# 00_EEG_AFE.net
KiCad netlist of a schematic drawn in Altium Designer
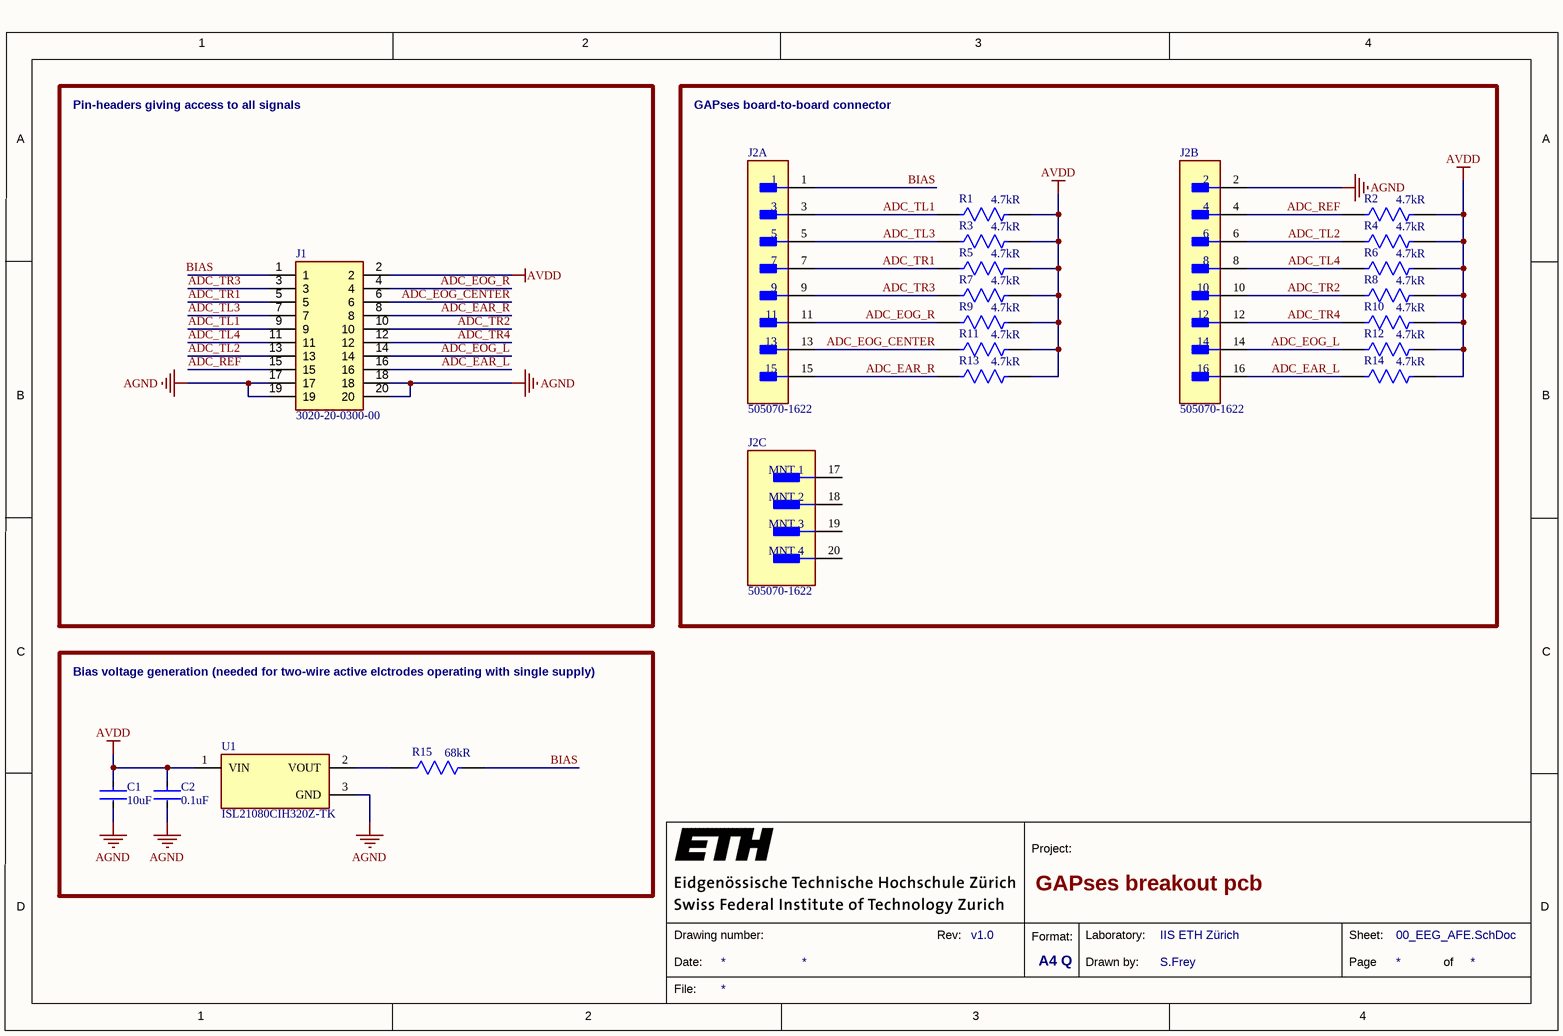
[diagram p0: 00_EEG_AFE.SchDoc]

(export (version "E")
  (design (tool "Eeschema 10.0.6"))
  (components
    (comp (ref "C1")
      (value "CL05A106MP8NUB8")
      (footprint "FP-CL07-IPC_C")
      (description "Cap Ceramic 10uF 10V X5R ±20% SMD 0402 +85°C Paper T/R")
      (fields (field (name "CAPACITANCE") "10uF") (field (name "TOLERANCE") "20%"))
      (libsource (lib "Altium Content Vault") (part "b4654b650e69147ec39a6b967a45e02"))
    )
    (comp (ref "C2")
      (value "CL05A104KA5NNNC")
      (footprint "FP-CL278-IPC_C")
      (description "Cap Ceramic 100nF 25V X5R ±10% SMD 0402 +85°C Paper T/R")
      (fields
        (field (name "VOLTAGE") "25V")
        (field (name "TOLERANCE") "10%")
        (field (name "CAPACITANCE") "0.1uF")
      )
      (libsource (lib "Altium Content Vault") (part "b4654b650e69147ec39a6b967a45e02"))
    )
    (comp (ref "J1")
      (value "3020-20-0300-00")
      (footprint "SamacSys:302020030000")
      (description "Connector")
      (libsource (lib "SamacSys") (part "3020-20-0300-00"))
    )
    (comp (ref "J2")
      (value "505070-1622")
      (footprint "FP-505070-1622-MFG")
      (description "CONN PLUG 16POS SMD GOLD")
      (libsource (lib "Altium Content Vault") (part "71c7bd868a703cb05f67e14b15c5ca9"))
    )
    (comp (ref "R1")
      (value "RR0510P-472-D")
      (footprint "FP-RR0510-IPC_C")
      (description "4.7kΩ ±0.5% 0.0625W 1/16W Chip Resistor 0402 (1005 Metric) Thin Film")
      (fields (field (name "TOLERANCE") "0.5%") (field (name "RESISTANCE") "4.7kR"))
      (libsource (lib "Altium Content Vault") (part "1029c3af85768c4190bb7ad29bc67b5"))
    )
    (comp (ref "R2")
      (value "RR0510P-472-D")
      (footprint "FP-RR0510-IPC_C")
      (description "4.7kΩ ±0.5% 0.0625W 1/16W Chip Resistor 0402 (1005 Metric) Thin Film")
      (fields (field (name "TOLERANCE") "0.5%") (field (name "RESISTANCE") "4.7kR"))
      (libsource (lib "Altium Content Vault") (part "1029c3af85768c4190bb7ad29bc67b5"))
    )
    (comp (ref "R3")
      (value "RR0510P-472-D")
      (footprint "FP-RR0510-IPC_C")
      (description "4.7kΩ ±0.5% 0.0625W 1/16W Chip Resistor 0402 (1005 Metric) Thin Film")
      (fields (field (name "TOLERANCE") "0.5%") (field (name "RESISTANCE") "4.7kR"))
      (libsource (lib "Altium Content Vault") (part "1029c3af85768c4190bb7ad29bc67b5"))
    )
    (comp (ref "R4")
      (value "RR0510P-472-D")
      (footprint "FP-RR0510-IPC_C")
      (description "4.7kΩ ±0.5% 0.0625W 1/16W Chip Resistor 0402 (1005 Metric) Thin Film")
      (fields (field (name "TOLERANCE") "0.5%") (field (name "RESISTANCE") "4.7kR"))
      (libsource (lib "Altium Content Vault") (part "1029c3af85768c4190bb7ad29bc67b5"))
    )
    (comp (ref "R5")
      (value "RR0510P-472-D")
      (footprint "FP-RR0510-IPC_C")
      (description "4.7kΩ ±0.5% 0.0625W 1/16W Chip Resistor 0402 (1005 Metric) Thin Film")
      (fields (field (name "TOLERANCE") "0.5%") (field (name "RESISTANCE") "4.7kR"))
      (libsource (lib "Altium Content Vault") (part "1029c3af85768c4190bb7ad29bc67b5"))
    )
    (comp (ref "R6")
      (value "RR0510P-472-D")
      (footprint "FP-RR0510-IPC_C")
      (description "4.7kΩ ±0.5% 0.0625W 1/16W Chip Resistor 0402 (1005 Metric) Thin Film")
      (fields (field (name "TOLERANCE") "0.5%") (field (name "RESISTANCE") "4.7kR"))
      (libsource (lib "Altium Content Vault") (part "1029c3af85768c4190bb7ad29bc67b5"))
    )
    (comp (ref "R7")
      (value "RR0510P-472-D")
      (footprint "FP-RR0510-IPC_C")
      (description "4.7kΩ ±0.5% 0.0625W 1/16W Chip Resistor 0402 (1005 Metric) Thin Film")
      (fields (field (name "TOLERANCE") "0.5%") (field (name "RESISTANCE") "4.7kR"))
      (libsource (lib "Altium Content Vault") (part "1029c3af85768c4190bb7ad29bc67b5"))
    )
    (comp (ref "R8")
      (value "RR0510P-472-D")
      (footprint "FP-RR0510-IPC_C")
      (description "4.7kΩ ±0.5% 0.0625W 1/16W Chip Resistor 0402 (1005 Metric) Thin Film")
      (fields (field (name "TOLERANCE") "0.5%") (field (name "RESISTANCE") "4.7kR"))
      (libsource (lib "Altium Content Vault") (part "1029c3af85768c4190bb7ad29bc67b5"))
    )
    (comp (ref "R9")
      (value "RR0510P-472-D")
      (footprint "FP-RR0510-IPC_C")
      (description "4.7kΩ ±0.5% 0.0625W 1/16W Chip Resistor 0402 (1005 Metric) Thin Film")
      (fields (field (name "TOLERANCE") "0.5%") (field (name "RESISTANCE") "4.7kR"))
      (libsource (lib "Altium Content Vault") (part "1029c3af85768c4190bb7ad29bc67b5"))
    )
    (comp (ref "R10")
      (value "RR0510P-472-D")
      (footprint "FP-RR0510-IPC_C")
      (description "4.7kΩ ±0.5% 0.0625W 1/16W Chip Resistor 0402 (1005 Metric) Thin Film")
      (fields (field (name "TOLERANCE") "0.5%") (field (name "RESISTANCE") "4.7kR"))
      (libsource (lib "Altium Content Vault") (part "1029c3af85768c4190bb7ad29bc67b5"))
    )
    (comp (ref "R11")
      (value "RR0510P-472-D")
      (footprint "FP-RR0510-IPC_C")
      (description "4.7kΩ ±0.5% 0.0625W 1/16W Chip Resistor 0402 (1005 Metric) Thin Film")
      (fields (field (name "TOLERANCE") "0.5%") (field (name "RESISTANCE") "4.7kR"))
      (libsource (lib "Altium Content Vault") (part "1029c3af85768c4190bb7ad29bc67b5"))
    )
    (comp (ref "R12")
      (value "RR0510P-472-D")
      (footprint "FP-RR0510-IPC_C")
      (description "4.7kΩ ±0.5% 0.0625W 1/16W Chip Resistor 0402 (1005 Metric) Thin Film")
      (fields (field (name "TOLERANCE") "0.5%") (field (name "RESISTANCE") "4.7kR"))
      (libsource (lib "Altium Content Vault") (part "1029c3af85768c4190bb7ad29bc67b5"))
    )
    (comp (ref "R13")
      (value "RR0510P-472-D")
      (footprint "FP-RR0510-IPC_C")
      (description "4.7kΩ ±0.5% 0.0625W 1/16W Chip Resistor 0402 (1005 Metric) Thin Film")
      (fields (field (name "TOLERANCE") "0.5%") (field (name "RESISTANCE") "4.7kR"))
      (libsource (lib "Altium Content Vault") (part "1029c3af85768c4190bb7ad29bc67b5"))
    )
    (comp (ref "R14")
      (value "RR0510P-472-D")
      (footprint "FP-RR0510-IPC_C")
      (description "4.7kΩ ±0.5% 0.0625W 1/16W Chip Resistor 0402 (1005 Metric) Thin Film")
      (fields (field (name "TOLERANCE") "0.5%") (field (name "RESISTANCE") "4.7kR"))
      (libsource (lib "Altium Content Vault") (part "1029c3af85768c4190bb7ad29bc67b5"))
    )
    (comp (ref "R15")
      (value "RR0510P-683-D")
      (footprint "FP-RR0510-MFG")
      (description "68kΩ ±0.5% 0.0625W 1/16W Chip Resistor 0402 (1005 Metric) Thin Film")
      (fields (field (name "TOLERANCE") "0.5%") (field (name "RESISTANCE") "68kR"))
      (libsource (lib "Altium Content Vault") (part "1029c3af85768c4190bb7ad29bc67b5"))
    )
    (comp (ref "U1")
      (value "ISL21080CIH320Z-TK")
      (footprint "FP-P3_064A-IPC_C")
      (description "IC VREF SERIES 0.3% SOT23-3")
      (fields (field (name "TOLERANCE") "0.3%"))
      (libsource (lib "Altium Content Vault") (part "d4f0b6a9f4a6a4d0e4630da6419d1e9"))
    )
  )
  (nets
    (net (code "1") (name "/ADC_EAR_L") (class "Default")
      (node (ref "J1") (pin "16") (pinfunction "16_16") (pintype "passive"))
      (node (ref "J2") (pin "16") (pinfunction "16_16") (pintype "passive"))
      (node (ref "R14") (pin "1") (pinfunction "1_1") (pintype "passive"))
    )
    (net (code "2") (name "/ADC_EAR_R") (class "Default")
      (node (ref "J1") (pin "8") (pinfunction "8_8") (pintype "passive"))
      (node (ref "J2") (pin "15") (pinfunction "15_15") (pintype "passive"))
      (node (ref "R13") (pin "1") (pinfunction "1_1") (pintype "passive"))
    )
    (net (code "3") (name "/ADC_EOG_CENTER") (class "Default")
      (node (ref "J1") (pin "6") (pinfunction "6_6") (pintype "passive"))
      (node (ref "J2") (pin "13") (pinfunction "13_13") (pintype "passive"))
      (node (ref "R11") (pin "1") (pinfunction "1_1") (pintype "passive"))
    )
    (net (code "4") (name "/ADC_EOG_L") (class "Default")
      (node (ref "J1") (pin "14") (pinfunction "14_14") (pintype "passive"))
      (node (ref "J2") (pin "14") (pinfunction "14_14") (pintype "passive"))
      (node (ref "R12") (pin "1") (pinfunction "1_1") (pintype "passive"))
    )
    (net (code "5") (name "/ADC_EOG_R") (class "Default")
      (node (ref "J1") (pin "4") (pinfunction "4_4") (pintype "passive"))
      (node (ref "J2") (pin "11") (pinfunction "11_11") (pintype "passive"))
      (node (ref "R9") (pin "1") (pinfunction "1_1") (pintype "passive"))
    )
    (net (code "6") (name "/ADC_REF") (class "Default")
      (node (ref "J1") (pin "15") (pinfunction "15_15") (pintype "passive"))
      (node (ref "J2") (pin "4") (pinfunction "4_4") (pintype "passive"))
      (node (ref "R2") (pin "1") (pinfunction "1_1") (pintype "passive"))
    )
    (net (code "7") (name "/ADC_TL1") (class "Default")
      (node (ref "J1") (pin "9") (pinfunction "9_9") (pintype "passive"))
      (node (ref "J2") (pin "3") (pinfunction "3_3") (pintype "passive"))
      (node (ref "R1") (pin "1") (pinfunction "1_1") (pintype "passive"))
    )
    (net (code "8") (name "/ADC_TL2") (class "Default")
      (node (ref "J1") (pin "13") (pinfunction "13_13") (pintype "passive"))
      (node (ref "J2") (pin "6") (pinfunction "6_6") (pintype "passive"))
      (node (ref "R4") (pin "1") (pinfunction "1_1") (pintype "passive"))
    )
    (net (code "9") (name "/ADC_TL3") (class "Default")
      (node (ref "J1") (pin "7") (pinfunction "7_7") (pintype "passive"))
      (node (ref "J2") (pin "5") (pinfunction "5_5") (pintype "passive"))
      (node (ref "R3") (pin "1") (pinfunction "1_1") (pintype "passive"))
    )
    (net (code "10") (name "/ADC_TL4") (class "Default")
      (node (ref "J1") (pin "11") (pinfunction "11_11") (pintype "passive"))
      (node (ref "J2") (pin "8") (pinfunction "8_8") (pintype "passive"))
      (node (ref "R6") (pin "1") (pinfunction "1_1") (pintype "passive"))
    )
    (net (code "11") (name "/ADC_TR1") (class "Default")
      (node (ref "J1") (pin "5") (pinfunction "5_5") (pintype "passive"))
      (node (ref "J2") (pin "7") (pinfunction "7_7") (pintype "passive"))
      (node (ref "R5") (pin "1") (pinfunction "1_1") (pintype "passive"))
    )
    (net (code "12") (name "/ADC_TR2") (class "Default")
      (node (ref "J1") (pin "10") (pinfunction "10_10") (pintype "passive"))
      (node (ref "J2") (pin "10") (pinfunction "10_10") (pintype "passive"))
      (node (ref "R8") (pin "1") (pinfunction "1_1") (pintype "passive"))
    )
    (net (code "13") (name "/ADC_TR3") (class "Default")
      (node (ref "J1") (pin "3") (pinfunction "3_3") (pintype "passive"))
      (node (ref "J2") (pin "9") (pinfunction "9_9") (pintype "passive"))
      (node (ref "R7") (pin "1") (pinfunction "1_1") (pintype "passive"))
    )
    (net (code "14") (name "/ADC_TR4") (class "Default")
      (node (ref "J1") (pin "12") (pinfunction "12_12") (pintype "passive"))
      (node (ref "J2") (pin "12") (pinfunction "12_12") (pintype "passive"))
      (node (ref "R10") (pin "1") (pinfunction "1_1") (pintype "passive"))
    )
    (net (code "15") (name "/BIAS") (class "Default")
      (node (ref "J1") (pin "1") (pinfunction "1_1") (pintype "passive"))
      (node (ref "J2") (pin "1") (pinfunction "1_1") (pintype "passive"))
      (node (ref "R15") (pin "2") (pinfunction "2_2") (pintype "passive"))
    )
    (net (code "16") (name "AGND") (class "Default")
      (node (ref "C1") (pin "2") (pinfunction "2_2") (pintype "passive"))
      (node (ref "C2") (pin "2") (pinfunction "2_2") (pintype "passive"))
      (node (ref "J1") (pin "17") (pinfunction "17_17") (pintype "passive"))
      (node (ref "J1") (pin "18") (pinfunction "18_18") (pintype "passive"))
      (node (ref "J1") (pin "19") (pinfunction "19_19") (pintype "passive"))
      (node (ref "J1") (pin "20") (pinfunction "20_20") (pintype "passive"))
      (node (ref "J2") (pin "2") (pinfunction "2_2") (pintype "passive"))
      (node (ref "U1") (pin "3") (pinfunction "GND_3") (pintype "power_in"))
    )
    (net (code "17") (name "AVDD") (class "Default")
      (node (ref "C1") (pin "1") (pinfunction "1_1") (pintype "passive"))
      (node (ref "C2") (pin "1") (pinfunction "1_1") (pintype "passive"))
      (node (ref "J1") (pin "2") (pinfunction "2_2") (pintype "passive"))
      (node (ref "R1") (pin "2") (pinfunction "2_2") (pintype "passive"))
      (node (ref "R10") (pin "2") (pinfunction "2_2") (pintype "passive"))
      (node (ref "R11") (pin "2") (pinfunction "2_2") (pintype "passive"))
      (node (ref "R12") (pin "2") (pinfunction "2_2") (pintype "passive"))
      (node (ref "R13") (pin "2") (pinfunction "2_2") (pintype "passive"))
      (node (ref "R14") (pin "2") (pinfunction "2_2") (pintype "passive"))
      (node (ref "R2") (pin "2") (pinfunction "2_2") (pintype "passive"))
      (node (ref "R3") (pin "2") (pinfunction "2_2") (pintype "passive"))
      (node (ref "R4") (pin "2") (pinfunction "2_2") (pintype "passive"))
      (node (ref "R5") (pin "2") (pinfunction "2_2") (pintype "passive"))
      (node (ref "R6") (pin "2") (pinfunction "2_2") (pintype "passive"))
      (node (ref "R7") (pin "2") (pinfunction "2_2") (pintype "passive"))
      (node (ref "R8") (pin "2") (pinfunction "2_2") (pintype "passive"))
      (node (ref "R9") (pin "2") (pinfunction "2_2") (pintype "passive"))
      (node (ref "U1") (pin "1") (pinfunction "VIN_1") (pintype "power_in"))
    )
    (net (code "18") (name "Net-(U1-VOUT)") (class "Default")
      (node (ref "R15") (pin "1") (pinfunction "1_1") (pintype "passive"))
      (node (ref "U1") (pin "2") (pinfunction "VOUT_2") (pintype "power_in"))
    )
    (net (code "19") (name "unconnected-(J2C-MNT_1-Pad17)") (class "Default")
      (node (ref "J2") (pin "17") (pinfunction "MNT_1_17") (pintype "passive"))
    )
    (net (code "20") (name "unconnected-(J2C-MNT_2-Pad18)") (class "Default")
      (node (ref "J2") (pin "18") (pinfunction "MNT_2_18") (pintype "passive"))
    )
    (net (code "21") (name "unconnected-(J2C-MNT_3-Pad19)") (class "Default")
      (node (ref "J2") (pin "19") (pinfunction "MNT_3_19") (pintype "passive"))
    )
    (net (code "22") (name "unconnected-(J2C-MNT_4-Pad20)") (class "Default")
      (node (ref "J2") (pin "20") (pinfunction "MNT_4_20") (pintype "passive"))
    )
  )
)
